# SmartSwitchControllerSlaves.net
KiCad netlist of a schematic drawn in EAGLE
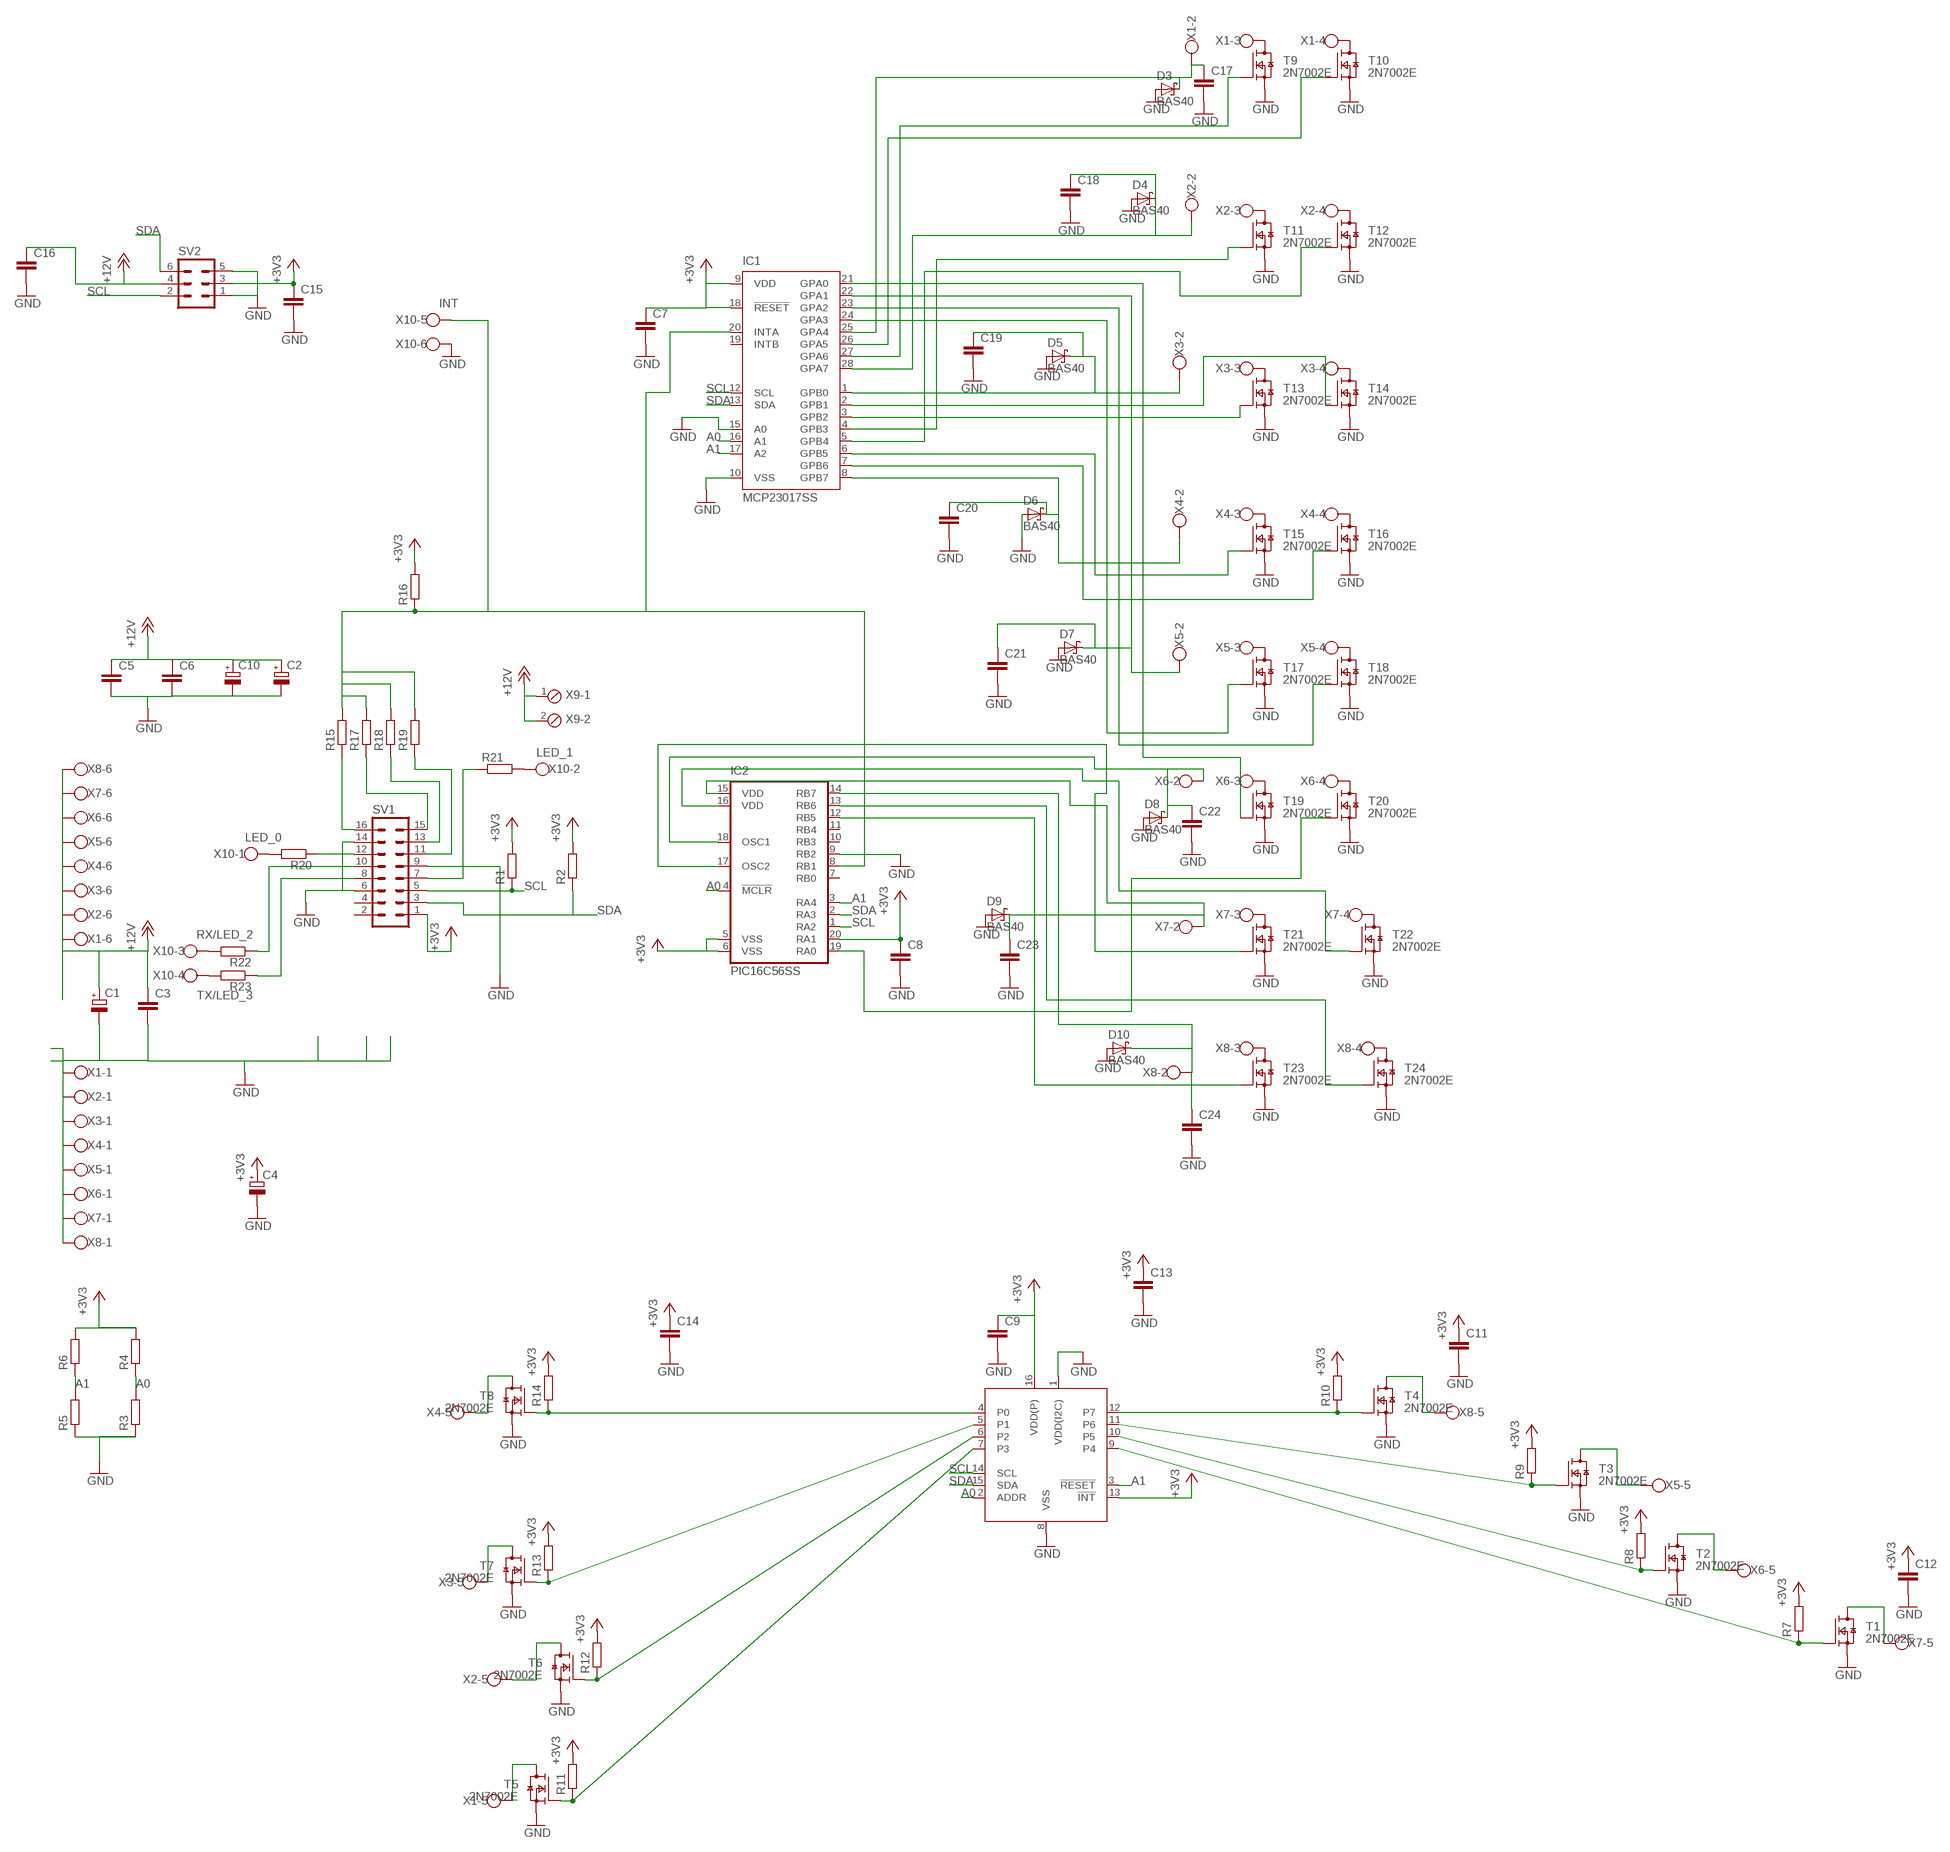
[diagram p0: schematic, sheet 1]

(export (version "E")
  (design (tool "Eeschema 10.0.6"))
  (components
    (comp (ref "C1")
      (value "CPOL-EUUD-6,3X7,7")
      (footprint "eagle-import:UD-6,3X7,7_NICHICON")
      (libsource (lib "eagle-import") (part "CPOL-EUUD-6,3X7,7"))
    )
    (comp (ref "C2")
      (value "CPOL-EUUD-6,3X7,7")
      (footprint "eagle-import:UD-6,3X7,7_NICHICON")
      (libsource (lib "eagle-import") (part "CPOL-EUUD-6,3X7,7"))
    )
    (comp (ref "C3")
      (value "C-EUC0603")
      (footprint "eagle-import:C0603")
      (libsource (lib "eagle-import") (part "C-EUC0603"))
    )
    (comp (ref "C4")
      (value "CPOL-EUUD-6,3X7,7")
      (footprint "eagle-import:UD-6,3X7,7_NICHICON")
      (libsource (lib "eagle-import") (part "CPOL-EUUD-6,3X7,7"))
    )
    (comp (ref "C5")
      (value "C-EUC0603")
      (footprint "eagle-import:C0603")
      (libsource (lib "eagle-import") (part "C-EUC0603"))
    )
    (comp (ref "C6")
      (value "C-EUC0805")
      (footprint "eagle-import:C0805")
      (libsource (lib "eagle-import") (part "C-EUC0805"))
    )
    (comp (ref "C7")
      (value "C-EUC0603")
      (footprint "eagle-import:C0603")
      (libsource (lib "eagle-import") (part "C-EUC0603"))
    )
    (comp (ref "C8")
      (value "C-EUC0603")
      (footprint "eagle-import:C0603")
      (libsource (lib "eagle-import") (part "C-EUC0603"))
    )
    (comp (ref "C9")
      (value "C-EUC0603")
      (footprint "eagle-import:C0603")
      (libsource (lib "eagle-import") (part "C-EUC0603"))
    )
    (comp (ref "C10")
      (value "CPOL-EUUD-6,3X7,7")
      (footprint "eagle-import:UD-6,3X7,7_NICHICON")
      (libsource (lib "eagle-import") (part "CPOL-EUUD-6,3X7,7"))
    )
    (comp (ref "C11")
      (value "C-EUC0603")
      (footprint "eagle-import:C0603")
      (libsource (lib "eagle-import") (part "C-EUC0603"))
    )
    (comp (ref "C12")
      (value "C-EUC0603")
      (footprint "eagle-import:C0603")
      (libsource (lib "eagle-import") (part "C-EUC0603"))
    )
    (comp (ref "C13")
      (value "C-EUC0805")
      (footprint "eagle-import:C0805")
      (libsource (lib "eagle-import") (part "C-EUC0805"))
    )
    (comp (ref "C14")
      (value "C-EUC0805")
      (footprint "eagle-import:C0805")
      (libsource (lib "eagle-import") (part "C-EUC0805"))
    )
    (comp (ref "C15")
      (value "C-EUC0805")
      (footprint "eagle-import:C0805")
      (libsource (lib "eagle-import") (part "C-EUC0805"))
    )
    (comp (ref "C16")
      (value "C-EUC0805")
      (footprint "eagle-import:C0805")
      (libsource (lib "eagle-import") (part "C-EUC0805"))
    )
    (comp (ref "C17")
      (value "C-EUC0805")
      (footprint "eagle-import:C0805")
      (libsource (lib "eagle-import") (part "C-EUC0805"))
    )
    (comp (ref "C18")
      (value "C-EUC0805")
      (footprint "eagle-import:C0805")
      (libsource (lib "eagle-import") (part "C-EUC0805"))
    )
    (comp (ref "C19")
      (value "C-EUC0805")
      (footprint "eagle-import:C0805")
      (libsource (lib "eagle-import") (part "C-EUC0805"))
    )
    (comp (ref "C20")
      (value "C-EUC0805")
      (footprint "eagle-import:C0805")
      (libsource (lib "eagle-import") (part "C-EUC0805"))
    )
    (comp (ref "C21")
      (value "C-EUC0805")
      (footprint "eagle-import:C0805")
      (libsource (lib "eagle-import") (part "C-EUC0805"))
    )
    (comp (ref "C22")
      (value "C-EUC0805")
      (footprint "eagle-import:C0805")
      (libsource (lib "eagle-import") (part "C-EUC0805"))
    )
    (comp (ref "C23")
      (value "C-EUC0805")
      (footprint "eagle-import:C0805")
      (libsource (lib "eagle-import") (part "C-EUC0805"))
    )
    (comp (ref "C24")
      (value "C-EUC0805")
      (footprint "eagle-import:C0805")
      (libsource (lib "eagle-import") (part "C-EUC0805"))
    )
    (comp (ref "D3")
      (value "BAS40")
      (footprint "eagle-import:SOT23")
      (libsource (lib "eagle-import") (part "BAS40"))
    )
    (comp (ref "D4")
      (value "BAS40")
      (footprint "eagle-import:SOT23")
      (libsource (lib "eagle-import") (part "BAS40"))
    )
    (comp (ref "D5")
      (value "BAS40")
      (footprint "eagle-import:SOT23")
      (libsource (lib "eagle-import") (part "BAS40"))
    )
    (comp (ref "D6")
      (value "BAS40")
      (footprint "eagle-import:SOT23")
      (libsource (lib "eagle-import") (part "BAS40"))
    )
    (comp (ref "D7")
      (value "BAS40")
      (footprint "eagle-import:SOT23")
      (libsource (lib "eagle-import") (part "BAS40"))
    )
    (comp (ref "D8")
      (value "BAS40")
      (footprint "eagle-import:SOT23")
      (libsource (lib "eagle-import") (part "BAS40"))
    )
    (comp (ref "D9")
      (value "BAS40")
      (footprint "eagle-import:SOT23")
      (libsource (lib "eagle-import") (part "BAS40"))
    )
    (comp (ref "D10")
      (value "BAS40")
      (footprint "eagle-import:SOT23")
      (libsource (lib "eagle-import") (part "BAS40"))
    )
    (comp (ref "IC1")
      (value "MCP23017SS")
      (footprint "eagle-import:SSOP28")
      (fields (field (name "MF") "MICROCHIP") (field (name "MPN") "MCP23017-E/SS"))
      (libsource (lib "eagle-import") (part "MCP23017SS"))
    )
    (comp (ref "IC2")
      (value "PIC16C56SS")
      (footprint "eagle-import:SSOP20")
      (fields (field (name "MF") "MICROCHIP") (field (name "MPN") "PIC16C56A-04/SS"))
      (libsource (lib "eagle-import") (part "PIC16C56SS"))
    )
    (comp (ref "R1")
      (value "R-EU_R0603")
      (footprint "eagle-import:R0603")
      (libsource (lib "eagle-import") (part "R-EU_R0603"))
    )
    (comp (ref "R2")
      (value "R-EU_R0603")
      (footprint "eagle-import:R0603")
      (libsource (lib "eagle-import") (part "R-EU_R0603"))
    )
    (comp (ref "R3")
      (value "R-EU_R0402")
      (footprint "eagle-import:R0402")
      (libsource (lib "eagle-import") (part "R-EU_R0402"))
    )
    (comp (ref "R4")
      (value "R-EU_R0402")
      (footprint "eagle-import:R0402")
      (libsource (lib "eagle-import") (part "R-EU_R0402"))
    )
    (comp (ref "R5")
      (value "R-EU_R0402")
      (footprint "eagle-import:R0402")
      (libsource (lib "eagle-import") (part "R-EU_R0402"))
    )
    (comp (ref "R6")
      (value "R-EU_R0402")
      (footprint "eagle-import:R0402")
      (libsource (lib "eagle-import") (part "R-EU_R0402"))
    )
    (comp (ref "R7")
      (value "R-EU_R0402")
      (footprint "eagle-import:R0402")
      (libsource (lib "eagle-import") (part "R-EU_R0402"))
    )
    (comp (ref "R8")
      (value "R-EU_R0402")
      (footprint "eagle-import:R0402")
      (libsource (lib "eagle-import") (part "R-EU_R0402"))
    )
    (comp (ref "R9")
      (value "R-EU_R0402")
      (footprint "eagle-import:R0402")
      (libsource (lib "eagle-import") (part "R-EU_R0402"))
    )
    (comp (ref "R10")
      (value "R-EU_R0402")
      (footprint "eagle-import:R0402")
      (libsource (lib "eagle-import") (part "R-EU_R0402"))
    )
    (comp (ref "R11")
      (value "R-EU_R0402")
      (footprint "eagle-import:R0402")
      (libsource (lib "eagle-import") (part "R-EU_R0402"))
    )
    (comp (ref "R12")
      (value "R-EU_R0402")
      (footprint "eagle-import:R0402")
      (libsource (lib "eagle-import") (part "R-EU_R0402"))
    )
    (comp (ref "R13")
      (value "R-EU_R0402")
      (footprint "eagle-import:R0402")
      (libsource (lib "eagle-import") (part "R-EU_R0402"))
    )
    (comp (ref "R14")
      (value "R-EU_R0402")
      (footprint "eagle-import:R0402")
      (libsource (lib "eagle-import") (part "R-EU_R0402"))
    )
    (comp (ref "R15")
      (value "R-EU_R0603")
      (footprint "eagle-import:R0603")
      (libsource (lib "eagle-import") (part "R-EU_R0603"))
    )
    (comp (ref "R16")
      (value "R-EU_R0603")
      (footprint "eagle-import:R0603")
      (libsource (lib "eagle-import") (part "R-EU_R0603"))
    )
    (comp (ref "R17")
      (value "R-EU_R0603")
      (footprint "eagle-import:R0603")
      (libsource (lib "eagle-import") (part "R-EU_R0603"))
    )
    (comp (ref "R18")
      (value "R-EU_R0603")
      (footprint "eagle-import:R0603")
      (libsource (lib "eagle-import") (part "R-EU_R0603"))
    )
    (comp (ref "R19")
      (value "R-EU_R0603")
      (footprint "eagle-import:R0603")
      (libsource (lib "eagle-import") (part "R-EU_R0603"))
    )
    (comp (ref "R20")
      (value "R-EU_R0603")
      (footprint "eagle-import:R0603")
      (libsource (lib "eagle-import") (part "R-EU_R0603"))
    )
    (comp (ref "R21")
      (value "R-EU_R0603")
      (footprint "eagle-import:R0603")
      (libsource (lib "eagle-import") (part "R-EU_R0603"))
    )
    (comp (ref "R22")
      (value "R-EU_R0603")
      (footprint "eagle-import:R0603")
      (libsource (lib "eagle-import") (part "R-EU_R0603"))
    )
    (comp (ref "R23")
      (value "R-EU_R0603")
      (footprint "eagle-import:R0603")
      (libsource (lib "eagle-import") (part "R-EU_R0603"))
    )
    (comp (ref "SV1")
      (value "MA08-2")
      (footprint "eagle-import:MA08-2")
      (libsource (lib "eagle-import") (part "MA08-2"))
    )
    (comp (ref "SV2")
      (value "MA03-2")
      (footprint "eagle-import:MA03-2")
      (libsource (lib "eagle-import") (part "MA03-2"))
    )
    (comp (ref "T1")
      (value "2N7002E")
      (footprint "eagle-import:SOT23")
      (libsource (lib "eagle-import") (part "2N7002E"))
    )
    (comp (ref "T2")
      (value "2N7002E")
      (footprint "eagle-import:SOT23")
      (libsource (lib "eagle-import") (part "2N7002E"))
    )
    (comp (ref "T3")
      (value "2N7002E")
      (footprint "eagle-import:SOT23")
      (libsource (lib "eagle-import") (part "2N7002E"))
    )
    (comp (ref "T4")
      (value "2N7002E")
      (footprint "eagle-import:SOT23")
      (libsource (lib "eagle-import") (part "2N7002E"))
    )
    (comp (ref "T5")
      (value "2N7002E")
      (footprint "eagle-import:SOT23")
      (libsource (lib "eagle-import") (part "2N7002E"))
    )
    (comp (ref "T6")
      (value "2N7002E")
      (footprint "eagle-import:SOT23")
      (libsource (lib "eagle-import") (part "2N7002E"))
    )
    (comp (ref "T7")
      (value "2N7002E")
      (footprint "eagle-import:SOT23")
      (libsource (lib "eagle-import") (part "2N7002E"))
    )
    (comp (ref "T8")
      (value "2N7002E")
      (footprint "eagle-import:SOT23")
      (libsource (lib "eagle-import") (part "2N7002E"))
    )
    (comp (ref "T9")
      (value "2N7002E")
      (footprint "eagle-import:SOT23")
      (libsource (lib "eagle-import") (part "2N7002E"))
    )
    (comp (ref "T10")
      (value "2N7002E")
      (footprint "eagle-import:SOT23")
      (libsource (lib "eagle-import") (part "2N7002E"))
    )
    (comp (ref "T11")
      (value "2N7002E")
      (footprint "eagle-import:SOT23")
      (libsource (lib "eagle-import") (part "2N7002E"))
    )
    (comp (ref "T12")
      (value "2N7002E")
      (footprint "eagle-import:SOT23")
      (libsource (lib "eagle-import") (part "2N7002E"))
    )
    (comp (ref "T13")
      (value "2N7002E")
      (footprint "eagle-import:SOT23")
      (libsource (lib "eagle-import") (part "2N7002E"))
    )
    (comp (ref "T14")
      (value "2N7002E")
      (footprint "eagle-import:SOT23")
      (libsource (lib "eagle-import") (part "2N7002E"))
    )
    (comp (ref "T15")
      (value "2N7002E")
      (footprint "eagle-import:SOT23")
      (libsource (lib "eagle-import") (part "2N7002E"))
    )
    (comp (ref "T16")
      (value "2N7002E")
      (footprint "eagle-import:SOT23")
      (libsource (lib "eagle-import") (part "2N7002E"))
    )
    (comp (ref "T17")
      (value "2N7002E")
      (footprint "eagle-import:SOT23")
      (libsource (lib "eagle-import") (part "2N7002E"))
    )
    (comp (ref "T18")
      (value "2N7002E")
      (footprint "eagle-import:SOT23")
      (libsource (lib "eagle-import") (part "2N7002E"))
    )
    (comp (ref "T19")
      (value "2N7002E")
      (footprint "eagle-import:SOT23")
      (libsource (lib "eagle-import") (part "2N7002E"))
    )
    (comp (ref "T20")
      (value "2N7002E")
      (footprint "eagle-import:SOT23")
      (libsource (lib "eagle-import") (part "2N7002E"))
    )
    (comp (ref "T21")
      (value "2N7002E")
      (footprint "eagle-import:SOT23")
      (libsource (lib "eagle-import") (part "2N7002E"))
    )
    (comp (ref "T22")
      (value "2N7002E")
      (footprint "eagle-import:SOT23")
      (libsource (lib "eagle-import") (part "2N7002E"))
    )
    (comp (ref "T23")
      (value "2N7002E")
      (footprint "eagle-import:SOT23")
      (libsource (lib "eagle-import") (part "2N7002E"))
    )
    (comp (ref "T24")
      (value "2N7002E")
      (footprint "eagle-import:SOT23")
      (libsource (lib "eagle-import") (part "2N7002E"))
    )
    (comp (ref "U1")
      (value "PCAL6408APW")
      (footprint "eagle-import:SOT403-1")
      (libsource (lib "eagle-import") (part "PCAL6408APW"))
    )
    (comp (ref "X1")
      (value "W237-6")
      (footprint "eagle-import:W237-6")
      (libsource (lib "eagle-import") (part "W237-6"))
    )
    (comp (ref "X2")
      (value "W237-6")
      (footprint "eagle-import:W237-6")
      (libsource (lib "eagle-import") (part "W237-6"))
    )
    (comp (ref "X3")
      (value "W237-6")
      (footprint "eagle-import:W237-6")
      (libsource (lib "eagle-import") (part "W237-6"))
    )
    (comp (ref "X4")
      (value "W237-6")
      (footprint "eagle-import:W237-6")
      (libsource (lib "eagle-import") (part "W237-6"))
    )
    (comp (ref "X5")
      (value "W237-6")
      (footprint "eagle-import:W237-6")
      (libsource (lib "eagle-import") (part "W237-6"))
    )
    (comp (ref "X6")
      (value "W237-6")
      (footprint "eagle-import:W237-6")
      (libsource (lib "eagle-import") (part "W237-6"))
    )
    (comp (ref "X7")
      (value "W237-6")
      (footprint "eagle-import:W237-6")
      (libsource (lib "eagle-import") (part "W237-6"))
    )
    (comp (ref "X8")
      (value "W237-6")
      (footprint "eagle-import:W237-6")
      (libsource (lib "eagle-import") (part "W237-6"))
    )
    (comp (ref "X9")
      (value "MPT2")
      (footprint "eagle-import:2POL254")
      (libsource (lib "eagle-import") (part "MPT2"))
    )
    (comp (ref "X10")
      (value "W237-6")
      (footprint "eagle-import:W237-6")
      (libsource (lib "eagle-import") (part "W237-6"))
    )
  )
  (nets
    (net (code "1") (name "+3V3") (class "Default")
      (node (ref "C11") (pin "1") (pinfunction "1_1") (pintype "passive"))
      (node (ref "C12") (pin "1") (pinfunction "1_1") (pintype "passive"))
      (node (ref "C13") (pin "1") (pinfunction "1_1") (pintype "passive"))
      (node (ref "C14") (pin "1") (pinfunction "1_1") (pintype "passive"))
      (node (ref "C15") (pin "1") (pinfunction "1_1") (pintype "passive"))
      (node (ref "C4") (pin "+") (pinfunction "+_+") (pintype "passive"))
      (node (ref "C7") (pin "1") (pinfunction "1_1") (pintype "passive"))
      (node (ref "C8") (pin "1") (pinfunction "1_1") (pintype "passive"))
      (node (ref "C9") (pin "1") (pinfunction "1_1") (pintype "passive"))
      (node (ref "IC1") (pin "18") (pinfunction "~{RESET}_18") (pintype "input"))
      (node (ref "IC1") (pin "9") (pinfunction "VDD_9") (pintype "power_in"))
      (node (ref "IC2") (pin "20") (pinfunction "RA1_20") (pintype "bidirectional"))
      (node (ref "IC2") (pin "5") (pinfunction "VSS_5") (pintype "power_in"))
      (node (ref "IC2") (pin "6") (pinfunction "VSS_6") (pintype "power_in"))
      (node (ref "R1") (pin "2") (pinfunction "2_2") (pintype "passive"))
      (node (ref "R10") (pin "2") (pinfunction "2_2") (pintype "passive"))
      (node (ref "R11") (pin "2") (pinfunction "2_2") (pintype "passive"))
      (node (ref "R12") (pin "2") (pinfunction "2_2") (pintype "passive"))
      (node (ref "R13") (pin "2") (pinfunction "2_2") (pintype "passive"))
      (node (ref "R14") (pin "2") (pinfunction "2_2") (pintype "passive"))
      (node (ref "R16") (pin "2") (pinfunction "2_2") (pintype "passive"))
      (node (ref "R2") (pin "2") (pinfunction "2_2") (pintype "passive"))
      (node (ref "R4") (pin "2") (pinfunction "2_2") (pintype "passive"))
      (node (ref "R6") (pin "2") (pinfunction "2_2") (pintype "passive"))
      (node (ref "R7") (pin "2") (pinfunction "2_2") (pintype "passive"))
      (node (ref "R8") (pin "2") (pinfunction "2_2") (pintype "passive"))
      (node (ref "R9") (pin "2") (pinfunction "2_2") (pintype "passive"))
      (node (ref "SV1") (pin "1") (pinfunction "1_1") (pintype "passive"))
      (node (ref "SV2") (pin "3") (pinfunction "3_3") (pintype "passive"))
      (node (ref "U1") (pin "13") (pinfunction "~{INT}_13") (pintype "output"))
      (node (ref "U1") (pin "16") (pinfunction "VDD(P)_16") (pintype "power_in"))
    )
    (net (code "2") (name "+12V") (class "Default")
      (node (ref "C1") (pin "+") (pinfunction "+_+") (pintype "passive"))
      (node (ref "C10") (pin "+") (pinfunction "+_+") (pintype "passive"))
      (node (ref "C16") (pin "1") (pinfunction "1_1") (pintype "passive"))
      (node (ref "C2") (pin "+") (pinfunction "+_+") (pintype "passive"))
      (node (ref "C3") (pin "1") (pinfunction "1_1") (pintype "passive"))
      (node (ref "C5") (pin "1") (pinfunction "1_1") (pintype "passive"))
      (node (ref "C6") (pin "1") (pinfunction "1_1") (pintype "passive"))
      (node (ref "SV2") (pin "4") (pinfunction "4_4") (pintype "passive"))
      (node (ref "X1") (pin "6") (pinfunction "KL_6") (pintype "passive"))
      (node (ref "X2") (pin "6") (pinfunction "KL_6") (pintype "passive"))
      (node (ref "X3") (pin "6") (pinfunction "KL_6") (pintype "passive"))
      (node (ref "X4") (pin "6") (pinfunction "KL_6") (pintype "passive"))
      (node (ref "X5") (pin "6") (pinfunction "KL_6") (pintype "passive"))
      (node (ref "X6") (pin "6") (pinfunction "KL_6") (pintype "passive"))
      (node (ref "X7") (pin "6") (pinfunction "KL_6") (pintype "passive"))
      (node (ref "X8") (pin "6") (pinfunction "KL_6") (pintype "passive"))
      (node (ref "X9") (pin "1") (pinfunction "1_1") (pintype "passive"))
      (node (ref "X9") (pin "2") (pinfunction "1_2") (pintype "passive"))
    )
    (net (code "3") (name "/A0") (class "Default")
      (node (ref "IC1") (pin "16") (pinfunction "A1_16") (pintype "input"))
      (node (ref "IC2") (pin "4") (pinfunction "~{MCLR}_4") (pintype "input"))
      (node (ref "R3") (pin "2") (pinfunction "2_2") (pintype "passive"))
      (node (ref "R4") (pin "1") (pinfunction "1_1") (pintype "passive"))
      (node (ref "U1") (pin "2") (pinfunction "ADDR_2") (pintype "input"))
    )
    (net (code "4") (name "/A1") (class "Default")
      (node (ref "IC1") (pin "17") (pinfunction "A2_17") (pintype "input"))
      (node (ref "IC2") (pin "3") (pinfunction "RA4_3") (pintype "bidirectional"))
      (node (ref "R5") (pin "2") (pinfunction "2_2") (pintype "passive"))
      (node (ref "R6") (pin "1") (pinfunction "1_1") (pintype "passive"))
      (node (ref "U1") (pin "3") (pinfunction "~{RESET}_3") (pintype "input"))
    )
    (net (code "5") (name "/SCL") (class "Default")
      (node (ref "IC1") (pin "12") (pinfunction "SCL_12") (pintype "input"))
      (node (ref "IC2") (pin "1") (pinfunction "RA2_1") (pintype "bidirectional"))
      (node (ref "R1") (pin "1") (pinfunction "1_1") (pintype "passive"))
      (node (ref "SV1") (pin "5") (pinfunction "5_5") (pintype "passive"))
      (node (ref "SV2") (pin "2") (pinfunction "2_2") (pintype "passive"))
      (node (ref "U1") (pin "14") (pinfunction "SCL_14") (pintype "bidirectional"))
    )
    (net (code "6") (name "/SDA") (class "Default")
      (node (ref "IC1") (pin "13") (pinfunction "SDA_13") (pintype "bidirectional"))
      (node (ref "IC2") (pin "2") (pinfunction "RA3_2") (pintype "bidirectional"))
      (node (ref "R2") (pin "1") (pinfunction "1_1") (pintype "passive"))
      (node (ref "SV1") (pin "3") (pinfunction "3_3") (pintype "passive"))
      (node (ref "SV2") (pin "6") (pinfunction "6_6") (pintype "passive"))
      (node (ref "U1") (pin "15") (pinfunction "SDA_15") (pintype "bidirectional"))
    )
    (net (code "7") (name "GND") (class "Default")
      (node (ref "C1") (pin "-") (pinfunction "-_-") (pintype "passive"))
      (node (ref "C10") (pin "-") (pinfunction "-_-") (pintype "passive"))
      (node (ref "C11") (pin "2") (pinfunction "2_2") (pintype "passive"))
      (node (ref "C12") (pin "2") (pinfunction "2_2") (pintype "passive"))
      (node (ref "C13") (pin "2") (pinfunction "2_2") (pintype "passive"))
      (node (ref "C14") (pin "2") (pinfunction "2_2") (pintype "passive"))
      (node (ref "C15") (pin "2") (pinfunction "2_2") (pintype "passive"))
      (node (ref "C16") (pin "2") (pinfunction "2_2") (pintype "passive"))
      (node (ref "C17") (pin "2") (pinfunction "2_2") (pintype "passive"))
      (node (ref "C18") (pin "2") (pinfunction "2_2") (pintype "passive"))
      (node (ref "C19") (pin "2") (pinfunction "2_2") (pintype "passive"))
      (node (ref "C2") (pin "-") (pinfunction "-_-") (pintype "passive"))
      (node (ref "C20") (pin "2") (pinfunction "2_2") (pintype "passive"))
      (node (ref "C21") (pin "2") (pinfunction "2_2") (pintype "passive"))
      (node (ref "C22") (pin "2") (pinfunction "2_2") (pintype "passive"))
      (node (ref "C23") (pin "2") (pinfunction "2_2") (pintype "passive"))
      (node (ref "C24") (pin "2") (pinfunction "2_2") (pintype "passive"))
      (node (ref "C3") (pin "2") (pinfunction "2_2") (pintype "passive"))
      (node (ref "C4") (pin "-") (pinfunction "-_-") (pintype "passive"))
      (node (ref "C5") (pin "2") (pinfunction "2_2") (pintype "passive"))
      (node (ref "C6") (pin "2") (pinfunction "2_2") (pintype "passive"))
      (node (ref "C7") (pin "2") (pinfunction "2_2") (pintype "passive"))
      (node (ref "C8") (pin "2") (pinfunction "2_2") (pintype "passive"))
      (node (ref "C9") (pin "2") (pinfunction "2_2") (pintype "passive"))
      (node (ref "D10") (pin "1") (pinfunction "A_1") (pintype "passive"))
      (node (ref "D3") (pin "1") (pinfunction "A_1") (pintype "passive"))
      (node (ref "D4") (pin "1") (pinfunction "A_1") (pintype "passive"))
      (node (ref "D5") (pin "1") (pinfunction "A_1") (pintype "passive"))
      (node (ref "D6") (pin "1") (pinfunction "A_1") (pintype "passive"))
      (node (ref "D7") (pin "1") (pinfunction "A_1") (pintype "passive"))
      (node (ref "D8") (pin "1") (pinfunction "A_1") (pintype "passive"))
      (node (ref "D9") (pin "1") (pinfunction "A_1") (pintype "passive"))
      (node (ref "IC1") (pin "10") (pinfunction "VSS_10") (pintype "power_in"))
      (node (ref "IC1") (pin "15") (pinfunction "A0_15") (pintype "input"))
      (node (ref "IC2") (pin "9") (pinfunction "RB2_9") (pintype "bidirectional"))
      (node (ref "R3") (pin "1") (pinfunction "1_1") (pintype "passive"))
      (node (ref "R5") (pin "1") (pinfunction "1_1") (pintype "passive"))
      (node (ref "SV1") (pin "14") (pinfunction "14_14") (pintype "passive"))
      (node (ref "SV1") (pin "6") (pinfunction "6_6") (pintype "passive"))
      (node (ref "SV1") (pin "9") (pinfunction "9_9") (pintype "passive"))
      (node (ref "SV2") (pin "1") (pinfunction "1_1") (pintype "passive"))
      (node (ref "SV2") (pin "5") (pinfunction "5_5") (pintype "passive"))
      (node (ref "T1") (pin "2") (pinfunction "S_2") (pintype "passive"))
      (node (ref "T10") (pin "2") (pinfunction "S_2") (pintype "passive"))
      (node (ref "T11") (pin "2") (pinfunction "S_2") (pintype "passive"))
      (node (ref "T12") (pin "2") (pinfunction "S_2") (pintype "passive"))
      (node (ref "T13") (pin "2") (pinfunction "S_2") (pintype "passive"))
      (node (ref "T14") (pin "2") (pinfunction "S_2") (pintype "passive"))
      (node (ref "T15") (pin "2") (pinfunction "S_2") (pintype "passive"))
      (node (ref "T16") (pin "2") (pinfunction "S_2") (pintype "passive"))
      (node (ref "T17") (pin "2") (pinfunction "S_2") (pintype "passive"))
      (node (ref "T18") (pin "2") (pinfunction "S_2") (pintype "passive"))
      (node (ref "T19") (pin "2") (pinfunction "S_2") (pintype "passive"))
      (node (ref "T2") (pin "2") (pinfunction "S_2") (pintype "passive"))
      (node (ref "T20") (pin "2") (pinfunction "S_2") (pintype "passive"))
      (node (ref "T21") (pin "2") (pinfunction "S_2") (pintype "passive"))
      (node (ref "T22") (pin "2") (pinfunction "S_2") (pintype "passive"))
      (node (ref "T23") (pin "2") (pinfunction "S_2") (pintype "passive"))
      (node (ref "T24") (pin "2") (pinfunction "S_2") (pintype "passive"))
      (node (ref "T3") (pin "2") (pinfunction "S_2") (pintype "passive"))
      (node (ref "T4") (pin "2") (pinfunction "S_2") (pintype "passive"))
      (node (ref "T5") (pin "2") (pinfunction "S_2") (pintype "passive"))
      (node (ref "T6") (pin "2") (pinfunction "S_2") (pintype "passive"))
      (node (ref "T7") (pin "2") (pinfunction "S_2") (pintype "passive"))
      (node (ref "T8") (pin "2") (pinfunction "S_2") (pintype "passive"))
      (node (ref "T9") (pin "2") (pinfunction "S_2") (pintype "passive"))
      (node (ref "U1") (pin "1") (pinfunction "VDD(I2C)_1") (pintype "power_in"))
      (node (ref "U1") (pin "8") (pinfunction "VSS_8") (pintype "bidirectional"))
      (node (ref "X1") (pin "1") (pinfunction "KL_1") (pintype "passive"))
      (node (ref "X10") (pin "6") (pinfunction "KL_6") (pintype "passive"))
      (node (ref "X2") (pin "1") (pinfunction "KL_1") (pintype "passive"))
      (node (ref "X3") (pin "1") (pinfunction "KL_1") (pintype "passive"))
      (node (ref "X4") (pin "1") (pinfunction "KL_1") (pintype "passive"))
      (node (ref "X5") (pin "1") (pinfunction "KL_1") (pintype "passive"))
      (node (ref "X6") (pin "1") (pinfunction "KL_1") (pintype "passive"))
      (node (ref "X7") (pin "1") (pinfunction "KL_1") (pintype "passive"))
      (node (ref "X8") (pin "1") (pinfunction "KL_1") (pintype "passive"))
    )
    (net (code "8") (name "Net-(D3-C)") (class "Default")
      (node (ref "C17") (pin "1") (pinfunction "1_1") (pintype "passive"))
      (node (ref "D3") (pin "3") (pinfunction "C_3") (pintype "passive"))
      (node (ref "IC1") (pin "25") (pinfunction "GPA4_25") (pintype "bidirectional"))
      (node (ref "X1") (pin "2") (pinfunction "KL_2") (pintype "passive"))
    )
    (net (code "9") (name "Net-(D4-C)") (class "Default")
      (node (ref "C18") (pin "1") (pinfunction "1_1") (pintype "passive"))
      (node (ref "D4") (pin "3") (pinfunction "C_3") (pintype "passive"))
      (node (ref "IC1") (pin "28") (pinfunction "GPA7_28") (pintype "bidirectional"))
      (node (ref "X2") (pin "2") (pinfunction "KL_2") (pintype "passive"))
    )
    (net (code "10") (name "Net-(D5-C)") (class "Default")
      (node (ref "C19") (pin "1") (pinfunction "1_1") (pintype "passive"))
      (node (ref "D5") (pin "3") (pinfunction "C_3") (pintype "passive"))
      (node (ref "IC1") (pin "1") (pinfunction "GPB0_1") (pintype "bidirectional"))
      (node (ref "X3") (pin "2") (pinfunction "KL_2") (pintype "passive"))
    )
    (net (code "11") (name "Net-(D6-C)") (class "Default")
      (node (ref "C20") (pin "1") (pinfunction "1_1") (pintype "passive"))
      (node (ref "D6") (pin "3") (pinfunction "C_3") (pintype "passive"))
      (node (ref "IC1") (pin "8") (pinfunction "GPB7_8") (pintype "bidirectional"))
      (node (ref "X4") (pin "2") (pinfunction "KL_2") (pintype "passive"))
    )
    (net (code "12") (name "Net-(D7-C)") (class "Default")
      (node (ref "C21") (pin "1") (pinfunction "1_1") (pintype "passive"))
      (node (ref "D7") (pin "3") (pinfunction "C_3") (pintype "passive"))
      (node (ref "IC1") (pin "22") (pinfunction "GPA1_22") (pintype "bidirectional"))
      (node (ref "X5") (pin "2") (pinfunction "KL_2") (pintype "passive"))
    )
    (net (code "13") (name "Net-(D8-C)") (class "Default")
      (node (ref "C22") (pin "1") (pinfunction "1_1") (pintype "passive"))
      (node (ref "D8") (pin "3") (pinfunction "C_3") (pintype "passive"))
      (node (ref "IC2") (pin "18") (pinfunction "OSC1_18") (pintype "input"))
      (node (ref "X6") (pin "2") (pinfunction "KL_2") (pintype "passive"))
    )
    (net (code "14") (name "Net-(D9-C)") (class "Default")
      (node (ref "C23") (pin "1") (pinfunction "1_1") (pintype "passive"))
      (node (ref "D9") (pin "3") (pinfunction "C_3") (pintype "passive"))
      (node (ref "IC2") (pin "15") (pinfunction "VDD_15") (pintype "power_in"))
      (node (ref "X7") (pin "2") (pinfunction "KL_2") (pintype "passive"))
    )
    (net (code "15") (name "Net-(D10-C)") (class "Default")
      (node (ref "C24") (pin "1") (pinfunction "1_1") (pintype "passive"))
      (node (ref "D10") (pin "3") (pinfunction "C_3") (pintype "passive"))
      (node (ref "IC2") (pin "14") (pinfunction "RB7_14") (pintype "bidirectional"))
      (node (ref "X8") (pin "2") (pinfunction "KL_2") (pintype "passive"))
    )
    (net (code "16") (name "Net-(IC1-GPA0)") (class "Default")
      (node (ref "IC1") (pin "21") (pinfunction "GPA0_21") (pintype "bidirectional"))
      (node (ref "T19") (pin "1") (pinfunction "G_1") (pintype "passive"))
    )
    (net (code "17") (name "Net-(IC1-GPA2)") (class "Default")
      (node (ref "IC1") (pin "23") (pinfunction "GPA2_23") (pintype "bidirectional"))
      (node (ref "T18") (pin "1") (pinfunction "G_1") (pintype "passive"))
    )
    (net (code "18") (name "Net-(IC1-GPA3)") (class "Default")
      (node (ref "IC1") (pin "24") (pinfunction "GPA3_24") (pintype "bidirectional"))
      (node (ref "T17") (pin "1") (pinfunction "G_1") (pintype "passive"))
    )
    (net (code "19") (name "Net-(IC1-GPA5)") (class "Default")
      (node (ref "IC1") (pin "26") (pinfunction "GPA5_26") (pintype "bidirectional"))
      (node (ref "T10") (pin "1") (pinfunction "G_1") (pintype "passive"))
    )
    (net (code "20") (name "Net-(IC1-GPA6)") (class "Default")
      (node (ref "IC1") (pin "27") (pinfunction "GPA6_27") (pintype "bidirectional"))
      (node (ref "T9") (pin "1") (pinfunction "G_1") (pintype "passive"))
    )
    (net (code "21") (name "Net-(IC1-GPB1)") (class "Default")
      (node (ref "IC1") (pin "2") (pinfunction "GPB1_2") (pintype "bidirectional"))
      (node (ref "T14") (pin "1") (pinfunction "G_1") (pintype "passive"))
    )
    (net (code "22") (name "Net-(IC1-GPB2)") (class "Default")
      (node (ref "IC1") (pin "3") (pinfunction "GPB2_3") (pintype "bidirectional"))
      (node (ref "T13") (pin "1") (pinfunction "G_1") (pintype "passive"))
    )
    (net (code "23") (name "Net-(IC1-GPB3)") (class "Default")
      (node (ref "IC1") (pin "4") (pinfunction "GPB3_4") (pintype "bidirectional"))
      (node (ref "T11") (pin "1") (pinfunction "G_1") (pintype "passive"))
    )
    (net (code "24") (name "Net-(IC1-GPB4)") (class "Default")
      (node (ref "IC1") (pin "5") (pinfunction "GPB4_5") (pintype "bidirectional"))
      (node (ref "T12") (pin "1") (pinfunction "G_1") (pintype "passive"))
    )
    (net (code "25") (name "Net-(IC1-GPB5)") (class "Default")
      (node (ref "IC1") (pin "6") (pinfunction "GPB5_6") (pintype "bidirectional"))
      (node (ref "T15") (pin "1") (pinfunction "G_1") (pintype "passive"))
    )
    (net (code "26") (name "Net-(IC1-GPB6)") (class "Default")
      (node (ref "IC1") (pin "7") (pinfunction "GPB6_7") (pintype "bidirectional"))
      (node (ref "T16") (pin "1") (pinfunction "G_1") (pintype "passive"))
    )
    (net (code "27") (name "Net-(IC1-INTA)") (class "Default")
      (node (ref "IC1") (pin "20") (pinfunction "INTA_20") (pintype "output"))
      (node (ref "IC2") (pin "8") (pinfunction "RB1_8") (pintype "bidirectional"))
      (node (ref "R15") (pin "2") (pinfunction "2_2") (pintype "passive"))
      (node (ref "R16") (pin "1") (pinfunction "1_1") (pintype "passive"))
      (node (ref "R17") (pin "2") (pinfunction "2_2") (pintype "passive"))
      (node (ref "R18") (pin "2") (pinfunction "2_2") (pintype "passive"))
      (node (ref "R19") (pin "2") (pinfunction "2_2") (pintype "passive"))
      (node (ref "X10") (pin "5") (pinfunction "KL_5") (pintype "passive"))
    )
    (net (code "28") (name "Net-(IC2-OSC2)") (class "Default")
      (node (ref "IC2") (pin "17") (pinfunction "OSC2_17") (pintype "output"))
      (node (ref "T21") (pin "1") (pinfunction "G_1") (pintype "passive"))
    )
    (net (code "29") (name "Net-(IC2-RA0)") (class "Default")
      (node (ref "IC2") (pin "19") (pinfunction "RA0_19") (pintype "bidirectional"))
      (node (ref "T20") (pin "1") (pinfunction "G_1") (pintype "passive"))
    )
    (net (code "30") (name "Net-(IC2-RB5)") (class "Default")
      (node (ref "IC2") (pin "12") (pinfunction "RB5_12") (pintype "bidirectional"))
      (node (ref "T23") (pin "1") (pinfunction "G_1") (pintype "passive"))
    )
    (net (code "31") (name "Net-(IC2-RB6)") (class "Default")
      (node (ref "IC2") (pin "13") (pinfunction "RB6_13") (pintype "bidirectional"))
      (node (ref "T24") (pin "1") (pinfunction "G_1") (pintype "passive"))
    )
    (net (code "32") (name "Net-(R15-Pad1)") (class "Default")
      (node (ref "R15") (pin "1") (pinfunction "1_1") (pintype "passive"))
      (node (ref "SV1") (pin "16") (pinfunction "16_16") (pintype "passive"))
    )
    (net (code "33") (name "Net-(R17-Pad1)") (class "Default")
      (node (ref "R17") (pin "1") (pinfunction "1_1") (pintype "passive"))
      (node (ref "SV1") (pin "15") (pinfunction "15_15") (pintype "passive"))
    )
    (net (code "34") (name "Net-(R18-Pad1)") (class "Default")
      (node (ref "R18") (pin "1") (pinfunction "1_1") (pintype "passive"))
      (node (ref "SV1") (pin "13") (pinfunction "13_13") (pintype "passive"))
    )
    (net (code "35") (name "Net-(R19-Pad1)") (class "Default")
      (node (ref "R19") (pin "1") (pinfunction "1_1") (pintype "passive"))
      (node (ref "SV1") (pin "11") (pinfunction "11_11") (pintype "passive"))
    )
    (net (code "36") (name "Net-(R20-Pad1)") (class "Default")
      (node (ref "R20") (pin "1") (pinfunction "1_1") (pintype "passive"))
      (node (ref "SV1") (pin "12") (pinfunction "12_12") (pintype "passive"))
    )
    (net (code "37") (name "Net-(R21-Pad1)") (class "Default")
      (node (ref "R21") (pin "1") (pinfunction "1_1") (pintype "passive"))
      (node (ref "SV1") (pin "7") (pinfunction "7_7") (pintype "passive"))
    )
    (net (code "38") (name "Net-(R22-Pad1)") (class "Default")
      (node (ref "R22") (pin "1") (pinfunction "1_1") (pintype "passive"))
      (node (ref "SV1") (pin "10") (pinfunction "10_10") (pintype "passive"))
    )
    (net (code "39") (name "Net-(R23-Pad1)") (class "Default")
      (node (ref "R23") (pin "1") (pinfunction "1_1") (pintype "passive"))
      (node (ref "SV1") (pin "8") (pinfunction "8_8") (pintype "passive"))
    )
    (net (code "40") (name "Net-(T1-D)") (class "Default")
      (node (ref "T1") (pin "3") (pinfunction "D_3") (pintype "passive"))
      (node (ref "X7") (pin "5") (pinfunction "KL_5") (pintype "passive"))
    )
    (net (code "41") (name "Net-(T1-G)") (class "Default")
      (node (ref "R7") (pin "1") (pinfunction "1_1") (pintype "passive"))
      (node (ref "T1") (pin "1") (pinfunction "G_1") (pintype "passive"))
      (node (ref "U1") (pin "9") (pinfunction "P4_9") (pintype "bidirectional"))
    )
    (net (code "42") (name "Net-(T2-D)") (class "Default")
      (node (ref "T2") (pin "3") (pinfunction "D_3") (pintype "passive"))
      (node (ref "X6") (pin "5") (pinfunction "KL_5") (pintype "passive"))
    )
    (net (code "43") (name "Net-(T2-G)") (class "Default")
      (node (ref "R8") (pin "1") (pinfunction "1_1") (pintype "passive"))
      (node (ref "T2") (pin "1") (pinfunction "G_1") (pintype "passive"))
      (node (ref "U1") (pin "10") (pinfunction "P5_10") (pintype "bidirectional"))
    )
    (net (code "44") (name "Net-(T3-D)") (class "Default")
      (node (ref "T3") (pin "3") (pinfunction "D_3") (pintype "passive"))
      (node (ref "X5") (pin "5") (pinfunction "KL_5") (pintype "passive"))
    )
    (net (code "45") (name "Net-(T3-G)") (class "Default")
      (node (ref "R9") (pin "1") (pinfunction "1_1") (pintype "passive"))
      (node (ref "T3") (pin "1") (pinfunction "G_1") (pintype "passive"))
      (node (ref "U1") (pin "11") (pinfunction "P6_11") (pintype "bidirectional"))
    )
    (net (code "46") (name "Net-(T4-D)") (class "Default")
      (node (ref "T4") (pin "3") (pinfunction "D_3") (pintype "passive"))
      (node (ref "X8") (pin "5") (pinfunction "KL_5") (pintype "passive"))
    )
    (net (code "47") (name "Net-(T4-G)") (class "Default")
      (node (ref "R10") (pin "1") (pinfunction "1_1") (pintype "passive"))
      (node (ref "T4") (pin "1") (pinfunction "G_1") (pintype "passive"))
      (node (ref "U1") (pin "12") (pinfunction "P7_12") (pintype "bidirectional"))
    )
    (net (code "48") (name "Net-(T5-D)") (class "Default")
      (node (ref "T5") (pin "3") (pinfunction "D_3") (pintype "passive"))
      (node (ref "X1") (pin "5") (pinfunction "KL_5") (pintype "passive"))
    )
    (net (code "49") (name "Net-(T5-G)") (class "Default")
      (node (ref "R11") (pin "1") (pinfunction "1_1") (pintype "passive"))
      (node (ref "T5") (pin "1") (pinfunction "G_1") (pintype "passive"))
      (node (ref "U1") (pin "7") (pinfunction "P3_7") (pintype "bidirectional"))
    )
    (net (code "50") (name "Net-(T6-D)") (class "Default")
      (node (ref "T6") (pin "3") (pinfunction "D_3") (pintype "passive"))
      (node (ref "X2") (pin "5") (pinfunction "KL_5") (pintype "passive"))
    )
    (net (code "51") (name "Net-(T6-G)") (class "Default")
      (node (ref "R12") (pin "1") (pinfunction "1_1") (pintype "passive"))
      (node (ref "T6") (pin "1") (pinfunction "G_1") (pintype "passive"))
      (node (ref "U1") (pin "6") (pinfunction "P2_6") (pintype "bidirectional"))
    )
    (net (code "52") (name "Net-(T7-D)") (class "Default")
      (node (ref "T7") (pin "3") (pinfunction "D_3") (pintype "passive"))
      (node (ref "X3") (pin "5") (pinfunction "KL_5") (pintype "passive"))
    )
    (net (code "53") (name "Net-(T7-G)") (class "Default")
      (node (ref "R13") (pin "1") (pinfunction "1_1") (pintype "passive"))
      (node (ref "T7") (pin "1") (pinfunction "G_1") (pintype "passive"))
      (node (ref "U1") (pin "5") (pinfunction "P1_5") (pintype "bidirectional"))
    )
    (net (code "54") (name "Net-(T8-D)") (class "Default")
      (node (ref "T8") (pin "3") (pinfunction "D_3") (pintype "passive"))
      (node (ref "X4") (pin "5") (pinfunction "KL_5") (pintype "passive"))
    )
    (net (code "55") (name "Net-(T8-G)") (class "Default")
      (node (ref "R14") (pin "1") (pinfunction "1_1") (pintype "passive"))
      (node (ref "T8") (pin "1") (pinfunction "G_1") (pintype "passive"))
      (node (ref "U1") (pin "4") (pinfunction "P0_4") (pintype "bidirectional"))
    )
    (net (code "56") (name "Net-(T9-D)") (class "Default")
      (node (ref "T9") (pin "3") (pinfunction "D_3") (pintype "passive"))
      (node (ref "X1") (pin "3") (pinfunction "KL_3") (pintype "passive"))
    )
    (net (code "57") (name "Net-(T10-D)") (class "Default")
      (node (ref "T10") (pin "3") (pinfunction "D_3") (pintype "passive"))
      (node (ref "X1") (pin "4") (pinfunction "KL_4") (pintype "passive"))
    )
    (net (code "58") (name "Net-(T11-D)") (class "Default")
      (node (ref "T11") (pin "3") (pinfunction "D_3") (pintype "passive"))
      (node (ref "X2") (pin "3") (pinfunction "KL_3") (pintype "passive"))
    )
    (net (code "59") (name "Net-(T12-D)") (class "Default")
      (node (ref "T12") (pin "3") (pinfunction "D_3") (pintype "passive"))
      (node (ref "X2") (pin "4") (pinfunction "KL_4") (pintype "passive"))
    )
    (net (code "60") (name "Net-(T13-D)") (class "Default")
      (node (ref "T13") (pin "3") (pinfunction "D_3") (pintype "passive"))
      (node (ref "X3") (pin "3") (pinfunction "KL_3") (pintype "passive"))
    )
    (net (code "61") (name "Net-(T14-D)") (class "Default")
      (node (ref "T14") (pin "3") (pinfunction "D_3") (pintype "passive"))
      (node (ref "X3") (pin "4") (pinfunction "KL_4") (pintype "passive"))
    )
    (net (code "62") (name "Net-(T15-D)") (class "Default")
      (node (ref "T15") (pin "3") (pinfunction "D_3") (pintype "passive"))
      (node (ref "X4") (pin "3") (pinfunction "KL_3") (pintype "passive"))
    )
    (net (code "63") (name "Net-(T16-D)") (class "Default")
      (node (ref "T16") (pin "3") (pinfunction "D_3") (pintype "passive"))
      (node (ref "X4") (pin "4") (pinfunction "KL_4") (pintype "passive"))
    )
    (net (code "64") (name "Net-(T17-D)") (class "Default")
      (node (ref "T17") (pin "3") (pinfunction "D_3") (pintype "passive"))
      (node (ref "X5") (pin "3") (pinfunction "KL_3") (pintype "passive"))
    )
    (net (code "65") (name "Net-(T18-D)") (class "Default")
      (node (ref "T18") (pin "3") (pinfunction "D_3") (pintype "passive"))
      (node (ref "X5") (pin "4") (pinfunction "KL_4") (pintype "passive"))
    )
    (net (code "66") (name "Net-(T19-D)") (class "Default")
      (node (ref "T19") (pin "3") (pinfunction "D_3") (pintype "passive"))
      (node (ref "X6") (pin "3") (pinfunction "KL_3") (pintype "passive"))
    )
    (net (code "67") (name "Net-(T20-D)") (class "Default")
      (node (ref "T20") (pin "3") (pinfunction "D_3") (pintype "passive"))
      (node (ref "X6") (pin "4") (pinfunction "KL_4") (pintype "passive"))
    )
    (net (code "68") (name "Net-(T21-D)") (class "Default")
      (node (ref "T21") (pin "3") (pinfunction "D_3") (pintype "passive"))
      (node (ref "X7") (pin "3") (pinfunction "KL_3") (pintype "passive"))
    )
    (net (code "69") (name "Net-(T22-D)") (class "Default")
      (node (ref "T22") (pin "3") (pinfunction "D_3") (pintype "passive"))
      (node (ref "X7") (pin "4") (pinfunction "KL_4") (pintype "passive"))
    )
    (net (code "70") (name "Net-(T22-G)") (class "Default")
      (node (ref "IC2") (pin "16") (pinfunction "VDD_16") (pintype "power_in"))
      (node (ref "T22") (pin "1") (pinfunction "G_1") (pintype "passive"))
    )
    (net (code "71") (name "Net-(T23-D)") (class "Default")
      (node (ref "T23") (pin "3") (pinfunction "D_3") (pintype "passive"))
      (node (ref "X8") (pin "3") (pinfunction "KL_3") (pintype "passive"))
    )
    (net (code "72") (name "Net-(T24-D)") (class "Default")
      (node (ref "T24") (pin "3") (pinfunction "D_3") (pintype "passive"))
      (node (ref "X8") (pin "4") (pinfunction "KL_4") (pintype "passive"))
    )
    (net (code "73") (name "Net-(X10A-KL)") (class "Default")
      (node (ref "R20") (pin "2") (pinfunction "2_2") (pintype "passive"))
      (node (ref "X10") (pin "1") (pinfunction "KL_1") (pintype "passive"))
    )
    (net (code "74") (name "Net-(X10B-KL)") (class "Default")
      (node (ref "R21") (pin "2") (pinfunction "2_2") (pintype "passive"))
      (node (ref "X10") (pin "2") (pinfunction "KL_2") (pintype "passive"))
    )
    (net (code "75") (name "Net-(X10C-KL)") (class "Default")
      (node (ref "R22") (pin "2") (pinfunction "2_2") (pintype "passive"))
      (node (ref "X10") (pin "3") (pinfunction "KL_3") (pintype "passive"))
    )
    (net (code "76") (name "Net-(X10D-KL)") (class "Default")
      (node (ref "R23") (pin "2") (pinfunction "2_2") (pintype "passive"))
      (node (ref "X10") (pin "4") (pinfunction "KL_4") (pintype "passive"))
    )
    (net (code "77") (name "unconnected-(IC1-INTB-Pad19)") (class "Default")
      (node (ref "IC1") (pin "19") (pinfunction "INTB_19") (pintype "output"))
    )
    (net (code "78") (name "unconnected-(IC2-RB0-Pad7)") (class "Default")
      (node (ref "IC2") (pin "7") (pinfunction "RB0_7") (pintype "bidirectional"))
    )
    (net (code "79") (name "unconnected-(IC2-RB3-Pad10)") (class "Default")
      (node (ref "IC2") (pin "10") (pinfunction "RB3_10") (pintype "bidirectional"))
    )
    (net (code "80") (name "unconnected-(IC2-RB4-Pad11)") (class "Default")
      (node (ref "IC2") (pin "11") (pinfunction "RB4_11") (pintype "bidirectional"))
    )
    (net (code "81") (name "unconnected-(SV1-Pad2)") (class "Default")
      (node (ref "SV1") (pin "2") (pinfunction "2_2") (pintype "passive"))
    )
    (net (code "82") (name "unconnected-(SV1-Pad4)") (class "Default")
      (node (ref "SV1") (pin "4") (pinfunction "4_4") (pintype "passive"))
    )
  )
)
